# Analog_Front-End.net
KiCad netlist of a schematic drawn in Altium Designer
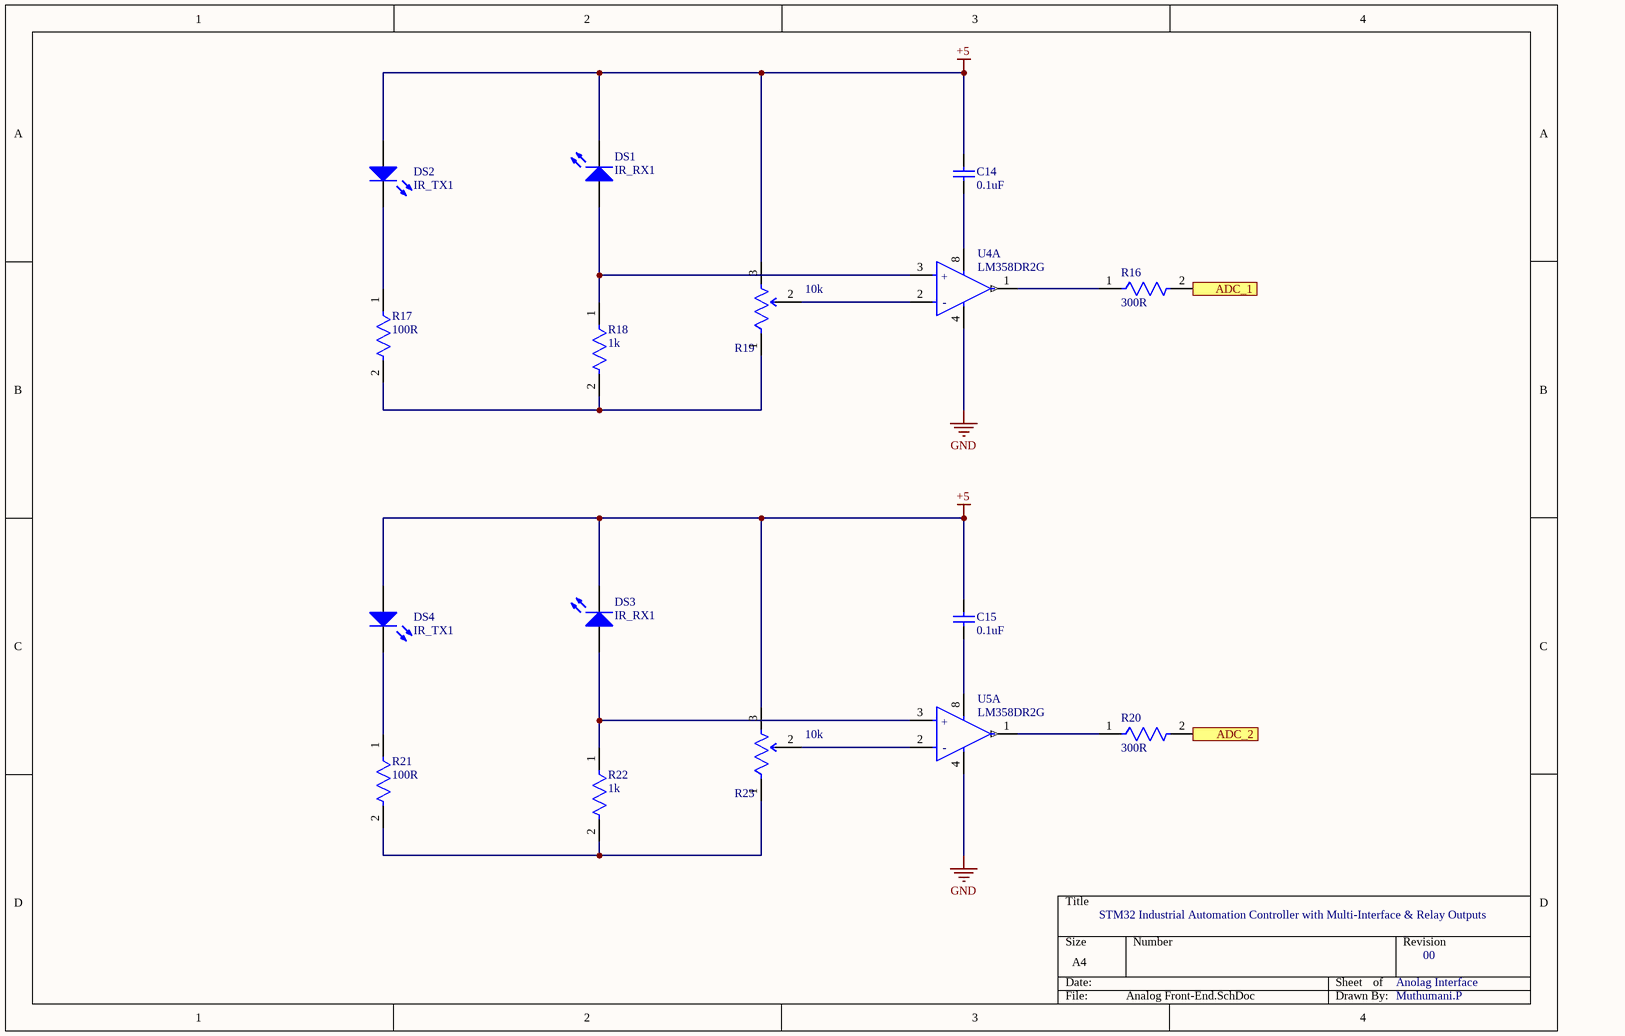
[diagram p0: Analog Front-End.SchDoc]

(export (version "E")
  (design (tool "Eeschema 10.0.6"))
  (components
    (comp (ref "C14")
      (value "0.1uF")
      (footprint "CAPC2013X145X50NL20T25")
      (fields (field (name "MANUFACTURER") "Kemet") (field (name "PART NUMBER") "C0805S104K5RACTU"))
      (libsource (lib "Altium Content Vault") (part "CAP"))
    )
    (comp (ref "C15")
      (value "0.1uF")
      (footprint "CAPC2013X145X50NL20T25")
      (fields (field (name "MANUFACTURER") "Kemet") (field (name "PART NUMBER") "C0805S104K5RACTU"))
      (libsource (lib "Altium Content Vault") (part "CAP"))
    )
    (comp (ref "DS1")
      (value "IR_RX1")
      (footprint "VISH-TSAL6200")
      (fields (field (name "MANUFACTURER") "Vishay"))
      (libsource (lib "Altium Content Vault") (part "LED-AK-2"))
    )
    (comp (ref "DS2")
      (value "IR_TX1")
      (footprint "VISH-TSAL6200")
      (fields (field (name "MANUFACTURER") "Vishay"))
      (libsource (lib "Altium Content Vault") (part "LED-AK-2"))
    )
    (comp (ref "DS3")
      (value "IR_RX1")
      (footprint "VISH-TSAL6200")
      (fields (field (name "MANUFACTURER") "Vishay"))
      (libsource (lib "Altium Content Vault") (part "LED-AK-2"))
    )
    (comp (ref "DS4")
      (value "IR_TX1")
      (footprint "VISH-TSAL6200")
      (fields (field (name "MANUFACTURER") "Vishay"))
      (libsource (lib "Altium Content Vault") (part "LED-AK-2"))
    )
    (comp (ref "R16")
      (value "300R")
      (footprint "FP-AC1206-MFG")
      (description "RES SMD 6.2K OHM 5% 1/4W 1206")
      (fields
        (field (name "OCTOPART") "https://octopart.com/ac1206jr-076k2l-yageo-30511322")
        (field (name "MANUFACTURER") "Yageo")
      )
      (libsource (lib "Altium Content Vault") (part "1029c3af85768c4190bb7ad29bc67b5"))
    )
    (comp (ref "R17")
      (value "100R")
      (footprint "FP-AC1206-MFG")
      (description "RES SMD 6.2K OHM 5% 1/4W 1206")
      (fields
        (field (name "OCTOPART") "https://octopart.com/ac1206jr-076k2l-yageo-30511322")
        (field (name "MANUFACTURER") "Yageo")
      )
      (libsource (lib "Altium Content Vault") (part "1029c3af85768c4190bb7ad29bc67b5"))
    )
    (comp (ref "R18")
      (value "1k")
      (footprint "FP-AC1206-MFG")
      (description "RES SMD 6.2K OHM 5% 1/4W 1206")
      (fields
        (field (name "OCTOPART") "https://octopart.com/ac1206jr-076k2l-yageo-30511322")
        (field (name "MANUFACTURER") "Yageo")
      )
      (libsource (lib "Altium Content Vault") (part "1029c3af85768c4190bb7ad29bc67b5"))
    )
    (comp (ref "R19")
      (value "10k")
      (footprint "FP-3296W-MFG")
      (description "TRIMMER 10K OHM 0.5W PC PIN TOP")
      (fields (field (name "TOLERANCE") "10%"))
      (libsource (lib "Altium Content Vault") (part "2dcfd2547301a7d3209a5e99acfd772"))
    )
    (comp (ref "R20")
      (value "300R")
      (footprint "FP-AC1206-MFG")
      (description "RES SMD 6.2K OHM 5% 1/4W 1206")
      (fields
        (field (name "OCTOPART") "https://octopart.com/ac1206jr-076k2l-yageo-30511322")
        (field (name "MANUFACTURER") "Yageo")
      )
      (libsource (lib "Altium Content Vault") (part "1029c3af85768c4190bb7ad29bc67b5"))
    )
    (comp (ref "R21")
      (value "100R")
      (footprint "FP-AC1206-MFG")
      (description "RES SMD 6.2K OHM 5% 1/4W 1206")
      (fields
        (field (name "OCTOPART") "https://octopart.com/ac1206jr-076k2l-yageo-30511322")
        (field (name "MANUFACTURER") "Yageo")
      )
      (libsource (lib "Altium Content Vault") (part "1029c3af85768c4190bb7ad29bc67b5"))
    )
    (comp (ref "R22")
      (value "1k")
      (footprint "FP-AC1206-MFG")
      (description "RES SMD 6.2K OHM 5% 1/4W 1206")
      (fields
        (field (name "OCTOPART") "https://octopart.com/ac1206jr-076k2l-yageo-30511322")
        (field (name "MANUFACTURER") "Yageo")
      )
      (libsource (lib "Altium Content Vault") (part "1029c3af85768c4190bb7ad29bc67b5"))
    )
    (comp (ref "R23")
      (value "10k")
      (footprint "FP-3296W-MFG")
      (description "TRIMMER 10K OHM 0.5W PC PIN TOP")
      (fields (field (name "TOLERANCE") "10%"))
      (libsource (lib "Altium Content Vault") (part "2dcfd2547301a7d3209a5e99acfd772"))
    )
    (comp (ref "U4")
      (value "LM358DR2G")
      (footprint "FP-751-07-IPC_C")
      (description "IC OPAMP GP 2 CIRCUIT 8SOIC")
      (libsource (lib "Altium Content Vault") (part "992a6607d1d88c80ee6b45e5ba6cb1b"))
    )
    (comp (ref "U5")
      (value "LM358DR2G")
      (footprint "FP-751-07-IPC_C")
      (description "IC OPAMP GP 2 CIRCUIT 8SOIC")
      (libsource (lib "Altium Content Vault") (part "992a6607d1d88c80ee6b45e5ba6cb1b"))
    )
  )
  (nets
    (net (code "1") (name "+5") (class "Default")
      (node (ref "C14") (pin "1") (pinfunction "1_1") (pintype "passive"))
      (node (ref "C15") (pin "1") (pinfunction "1_1") (pintype "passive"))
      (node (ref "DS1") (pin "2") (pinfunction "K_2") (pintype "passive"))
      (node (ref "DS2") (pin "1") (pinfunction "A_1") (pintype "passive"))
      (node (ref "DS3") (pin "2") (pinfunction "K_2") (pintype "passive"))
      (node (ref "DS4") (pin "1") (pinfunction "A_1") (pintype "passive"))
      (node (ref "R19") (pin "3") (pinfunction "CW_3") (pintype "passive"))
      (node (ref "R23") (pin "3") (pinfunction "CW_3") (pintype "passive"))
    )
    (net (code "2") (name "/ADC_1") (class "Default")
      (node (ref "R16") (pin "2") (pinfunction "2_2") (pintype "passive"))
    )
    (net (code "3") (name "/ADC_2") (class "Default")
      (node (ref "R20") (pin "2") (pinfunction "2_2") (pintype "passive"))
    )
    (net (code "4") (name "GND") (class "Default")
      (node (ref "U4") (pin "4") (pinfunction "VEE/GND_4") (pintype "power_in"))
      (node (ref "U5") (pin "4") (pinfunction "VEE/GND_4") (pintype "power_in"))
    )
    (net (code "5") (name "Net-(DS1-A)") (class "Default")
      (node (ref "DS1") (pin "1") (pinfunction "A_1") (pintype "passive"))
      (node (ref "R18") (pin "1") (pinfunction "1_1") (pintype "passive"))
      (node (ref "U4") (pin "3") (pinfunction "INPUT_A+_3") (pintype "tri_state"))
    )
    (net (code "6") (name "Net-(DS2-K)") (class "Default")
      (node (ref "DS2") (pin "2") (pinfunction "K_2") (pintype "passive"))
      (node (ref "R17") (pin "1") (pinfunction "1_1") (pintype "passive"))
    )
    (net (code "7") (name "Net-(DS3-A)") (class "Default")
      (node (ref "DS3") (pin "1") (pinfunction "A_1") (pintype "passive"))
      (node (ref "R22") (pin "1") (pinfunction "1_1") (pintype "passive"))
      (node (ref "U5") (pin "3") (pinfunction "INPUT_A+_3") (pintype "tri_state"))
    )
    (net (code "8") (name "Net-(DS4-K)") (class "Default")
      (node (ref "DS4") (pin "2") (pinfunction "K_2") (pintype "passive"))
      (node (ref "R21") (pin "1") (pinfunction "1_1") (pintype "passive"))
    )
    (net (code "9") (name "Net-(R19-CCW)") (class "Default")
      (node (ref "R17") (pin "2") (pinfunction "2_2") (pintype "passive"))
      (node (ref "R18") (pin "2") (pinfunction "2_2") (pintype "passive"))
      (node (ref "R19") (pin "1") (pinfunction "CCW_1") (pintype "passive"))
    )
    (net (code "10") (name "Net-(R19-WIPER)") (class "Default")
      (node (ref "R19") (pin "2") (pinfunction "WIPER_2") (pintype "passive"))
      (node (ref "U4") (pin "2") (pinfunction "INPUT_A-_2") (pintype "tri_state"))
    )
    (net (code "11") (name "Net-(R23-CCW)") (class "Default")
      (node (ref "R21") (pin "2") (pinfunction "2_2") (pintype "passive"))
      (node (ref "R22") (pin "2") (pinfunction "2_2") (pintype "passive"))
      (node (ref "R23") (pin "1") (pinfunction "CCW_1") (pintype "passive"))
    )
    (net (code "12") (name "Net-(R23-WIPER)") (class "Default")
      (node (ref "R23") (pin "2") (pinfunction "WIPER_2") (pintype "passive"))
      (node (ref "U5") (pin "2") (pinfunction "INPUT_A-_2") (pintype "tri_state"))
    )
    (net (code "13") (name "Net-(U4A-OUTPUT_A)") (class "Default")
      (node (ref "R16") (pin "1") (pinfunction "1_1") (pintype "passive"))
      (node (ref "U4") (pin "1") (pinfunction "OUTPUT_A_1") (pintype "output"))
    )
    (net (code "14") (name "Net-(U4A-VCC)") (class "Default")
      (node (ref "C14") (pin "2") (pinfunction "2_2") (pintype "passive"))
      (node (ref "U4") (pin "8") (pinfunction "VCC_8") (pintype "power_in"))
    )
    (net (code "15") (name "Net-(U5A-OUTPUT_A)") (class "Default")
      (node (ref "R20") (pin "1") (pinfunction "1_1") (pintype "passive"))
      (node (ref "U5") (pin "1") (pinfunction "OUTPUT_A_1") (pintype "output"))
    )
    (net (code "16") (name "Net-(U5A-VCC)") (class "Default")
      (node (ref "C15") (pin "2") (pinfunction "2_2") (pintype "passive"))
      (node (ref "U5") (pin "8") (pinfunction "VCC_8") (pintype "power_in"))
    )
  )
)
